# ELWireProximityController.net
KiCad netlist of a schematic drawn in EAGLE
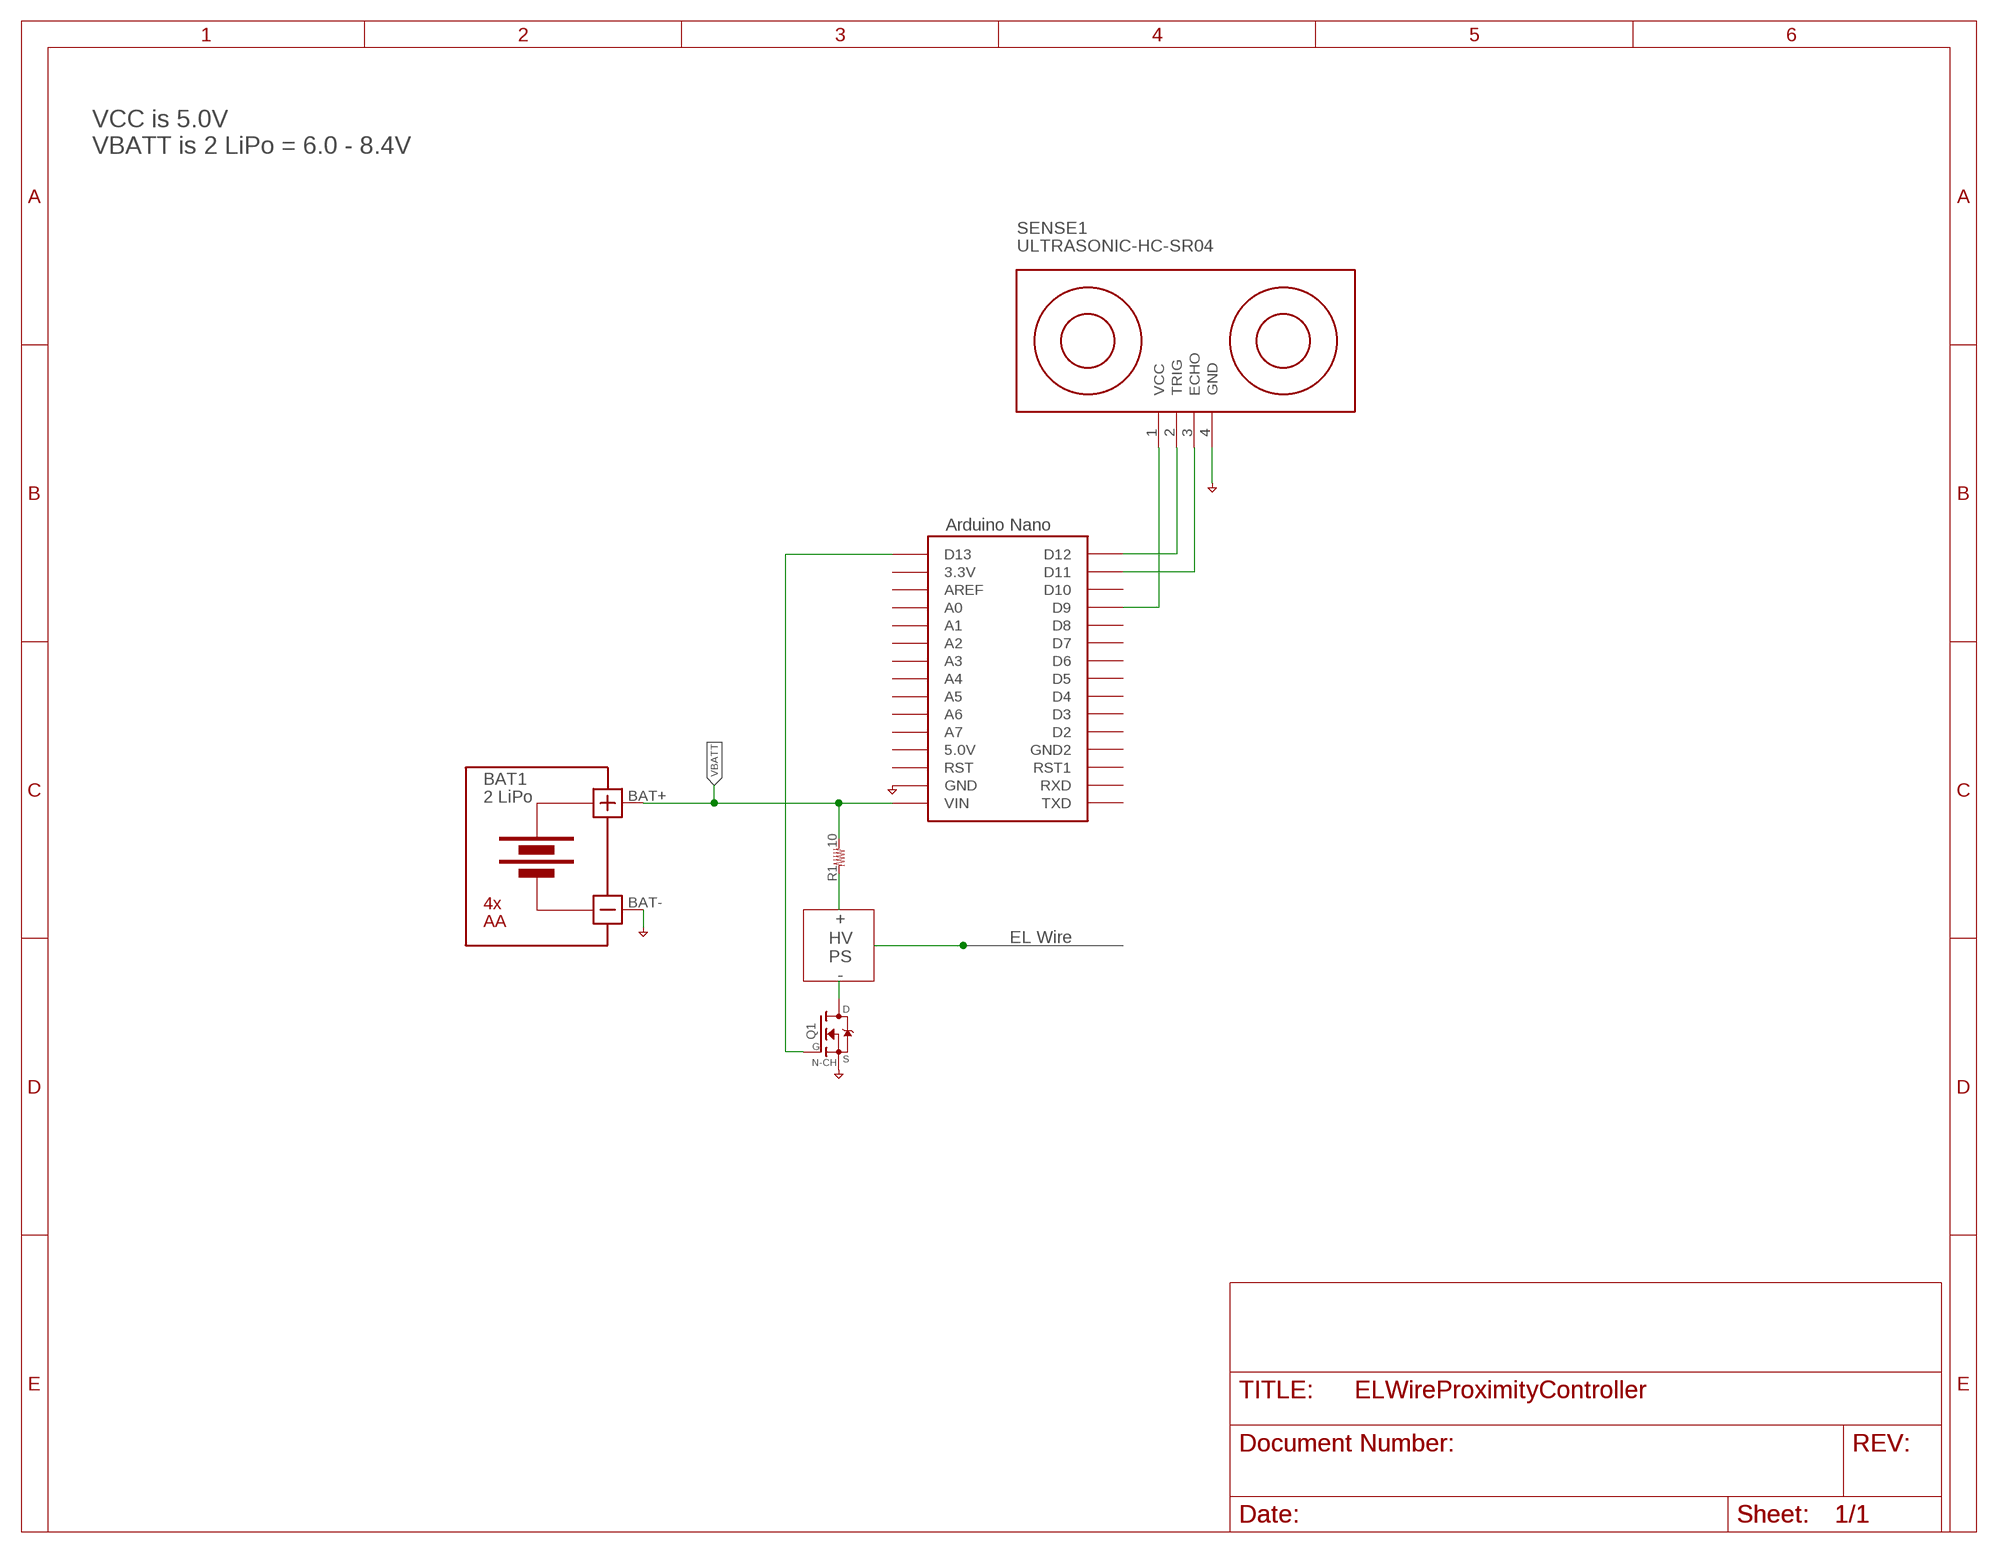
[diagram p0: schematic, sheet 1]

(export (version "E")
  (design (tool "Eeschema 10.0.6"))
  (components
    (comp (ref "BAT1")
      (value "2 LiPo")
      (footprint "eagle-import:BATTERY-HOLDER-2AA")
      (libsource (lib "eagle-import") (part "BATTERY-HOLDER-2AA"))
    )
    (comp (ref "Q1")
      (value "FET-NCH-SOT23")
      (footprint "eagle-import:SOT23-3")
      (libsource (lib "eagle-import") (part "FET-NCH-SOT23"))
    )
    (comp (ref "R1")
      (value "10")
      (footprint "eagle-import:R-THRU-H-0.4")
      (libsource (lib "eagle-import") (part "R-THRU-H-0.4"))
    )
    (comp (ref "SENSE1")
      (value "ULTRASONIC-HC-SR04")
      (footprint "eagle-import:ULTRASONIC-HC-SR04")
      (libsource (lib "eagle-import") (part "ULTRASONIC-HC-SR04"))
    )
    (comp (ref "U$1")
      (value "NANO")
      (footprint "eagle-import:NANO")
      (libsource (lib "eagle-import") (part "NANO"))
    )
  )
  (nets
    (net (code "1") (name "GND") (class "Default")
      (node (ref "BAT1") (pin "BAT-") (pinfunction "BAT-_BAT-") (pintype "power_in"))
      (node (ref "Q1") (pin "2") (pinfunction "S_2") (pintype "passive"))
      (node (ref "SENSE1") (pin "4") (pinfunction "GND_4") (pintype "power_in"))
      (node (ref "U$1") (pin "GND") (pinfunction "GND_GND") (pintype "bidirectional"))
    )
    (net (code "2") (name "Net-(Q1-G)") (class "Default")
      (node (ref "Q1") (pin "1") (pinfunction "G_1") (pintype "passive"))
      (node (ref "U$1") (pin "D13") (pinfunction "D13_D13") (pintype "bidirectional"))
    )
    (net (code "3") (name "Net-(SENSE1-ECHO)") (class "Default")
      (node (ref "SENSE1") (pin "3") (pinfunction "ECHO_3") (pintype "output"))
      (node (ref "U$1") (pin "D11") (pinfunction "D11_D11") (pintype "bidirectional"))
    )
    (net (code "4") (name "Net-(SENSE1-TRIG)") (class "Default")
      (node (ref "SENSE1") (pin "2") (pinfunction "TRIG_2") (pintype "input"))
      (node (ref "U$1") (pin "D12") (pinfunction "D12_D12") (pintype "bidirectional"))
    )
    (net (code "5") (name "Net-(SENSE1-VCC)") (class "Default")
      (node (ref "SENSE1") (pin "1") (pinfunction "VCC_1") (pintype "power_in"))
      (node (ref "U$1") (pin "D9") (pinfunction "D9_D9") (pintype "bidirectional"))
    )
    (net (code "6") (name "VBATT") (class "Default")
      (node (ref "BAT1") (pin "BAT+") (pinfunction "BAT+_BAT+") (pintype "power_in"))
      (node (ref "R1") (pin "2") (pinfunction "2_2") (pintype "passive"))
      (node (ref "U$1") (pin "RAW") (pinfunction "VIN_RAW") (pintype "bidirectional"))
    )
    (net (code "7") (name "unconnected-(Q1-D-Pad3)") (class "Default")
      (node (ref "Q1") (pin "3") (pinfunction "D_3") (pintype "passive"))
    )
    (net (code "8") (name "unconnected-(R1-Pad1)") (class "Default")
      (node (ref "R1") (pin "1") (pinfunction "1_1") (pintype "passive"))
    )
    (net (code "9") (name "unconnected-(U$1-5.0V-Pad5V)") (class "Default")
      (node (ref "U$1") (pin "5V") (pinfunction "5.0V_5V") (pintype "bidirectional"))
    )
    (net (code "10") (name "unconnected-(U$1-GND2-PadGND1)") (class "Default")
      (node (ref "U$1") (pin "GND1") (pinfunction "GND2_GND1") (pintype "bidirectional"))
    )
    (net (code "11") (name "unconnected-(U$1-Pad3.3V)") (class "Default")
      (node (ref "U$1") (pin "3.3V") (pinfunction "3.3V_3.3V") (pintype "bidirectional"))
    )
    (net (code "12") (name "unconnected-(U$1-PadA0)") (class "Default")
      (node (ref "U$1") (pin "A0") (pinfunction "A0_A0") (pintype "bidirectional"))
    )
    (net (code "13") (name "unconnected-(U$1-PadA1)") (class "Default")
      (node (ref "U$1") (pin "A1") (pinfunction "A1_A1") (pintype "bidirectional"))
    )
    (net (code "14") (name "unconnected-(U$1-PadA2)") (class "Default")
      (node (ref "U$1") (pin "A2") (pinfunction "A2_A2") (pintype "bidirectional"))
    )
    (net (code "15") (name "unconnected-(U$1-PadA3)") (class "Default")
      (node (ref "U$1") (pin "A3") (pinfunction "A3_A3") (pintype "bidirectional"))
    )
    (net (code "16") (name "unconnected-(U$1-PadA4)") (class "Default")
      (node (ref "U$1") (pin "A4") (pinfunction "A4_A4") (pintype "bidirectional"))
    )
    (net (code "17") (name "unconnected-(U$1-PadA5)") (class "Default")
      (node (ref "U$1") (pin "A5") (pinfunction "A5_A5") (pintype "bidirectional"))
    )
    (net (code "18") (name "unconnected-(U$1-PadA6)") (class "Default")
      (node (ref "U$1") (pin "A6") (pinfunction "A6_A6") (pintype "bidirectional"))
    )
    (net (code "19") (name "unconnected-(U$1-PadA7)") (class "Default")
      (node (ref "U$1") (pin "A7") (pinfunction "A7_A7") (pintype "bidirectional"))
    )
    (net (code "20") (name "unconnected-(U$1-PadAREF)") (class "Default")
      (node (ref "U$1") (pin "AREF") (pinfunction "AREF_AREF") (pintype "bidirectional"))
    )
    (net (code "21") (name "unconnected-(U$1-PadD2)") (class "Default")
      (node (ref "U$1") (pin "D2") (pinfunction "D2_D2") (pintype "bidirectional"))
    )
    (net (code "22") (name "unconnected-(U$1-PadD3)") (class "Default")
      (node (ref "U$1") (pin "D3") (pinfunction "D3_D3") (pintype "bidirectional"))
    )
    (net (code "23") (name "unconnected-(U$1-PadD4)") (class "Default")
      (node (ref "U$1") (pin "D4") (pinfunction "D4_D4") (pintype "bidirectional"))
    )
    (net (code "24") (name "unconnected-(U$1-PadD5)") (class "Default")
      (node (ref "U$1") (pin "D5") (pinfunction "D5_D5") (pintype "bidirectional"))
    )
    (net (code "25") (name "unconnected-(U$1-PadD6)") (class "Default")
      (node (ref "U$1") (pin "D6") (pinfunction "D6_D6") (pintype "bidirectional"))
    )
    (net (code "26") (name "unconnected-(U$1-PadD7)") (class "Default")
      (node (ref "U$1") (pin "D7") (pinfunction "D7_D7") (pintype "bidirectional"))
    )
    (net (code "27") (name "unconnected-(U$1-PadD8)") (class "Default")
      (node (ref "U$1") (pin "D8") (pinfunction "D8_D8") (pintype "bidirectional"))
    )
    (net (code "28") (name "unconnected-(U$1-PadD10)") (class "Default")
      (node (ref "U$1") (pin "D10") (pinfunction "D10_D10") (pintype "bidirectional"))
    )
    (net (code "29") (name "unconnected-(U$1-PadICSP1)") (class "Default")
      (node (ref "U$1") (pin "ICSP1") (pinfunction "ICSP1_ICSP1") (pintype "bidirectional"))
    )
    (net (code "30") (name "unconnected-(U$1-PadICSP2)") (class "Default")
      (node (ref "U$1") (pin "ICSP2") (pinfunction "ICSP2_ICSP2") (pintype "bidirectional"))
    )
    (net (code "31") (name "unconnected-(U$1-PadICSP3)") (class "Default")
      (node (ref "U$1") (pin "ICSP3") (pinfunction "ICSP3_ICSP3") (pintype "bidirectional"))
    )
    (net (code "32") (name "unconnected-(U$1-PadICSP4)") (class "Default")
      (node (ref "U$1") (pin "ICSP4") (pinfunction "ICSP4_ICSP4") (pintype "bidirectional"))
    )
    (net (code "33") (name "unconnected-(U$1-PadICSP5)") (class "Default")
      (node (ref "U$1") (pin "ICSP5") (pinfunction "ICSP5_ICSP5") (pintype "bidirectional"))
    )
    (net (code "34") (name "unconnected-(U$1-PadICSP6)") (class "Default")
      (node (ref "U$1") (pin "ICSP6") (pinfunction "ICSP6_ICSP6") (pintype "bidirectional"))
    )
    (net (code "35") (name "unconnected-(U$1-PadRST)") (class "Default")
      (node (ref "U$1") (pin "RST") (pinfunction "RST_RST") (pintype "bidirectional"))
    )
    (net (code "36") (name "unconnected-(U$1-PadRST1)") (class "Default")
      (node (ref "U$1") (pin "RST1") (pinfunction "RST1_RST1") (pintype "bidirectional"))
    )
    (net (code "37") (name "unconnected-(U$1-RXD-PadRX1)") (class "Default")
      (node (ref "U$1") (pin "RX1") (pinfunction "RXD_RX1") (pintype "bidirectional"))
    )
    (net (code "38") (name "unconnected-(U$1-TXD-PadTX0)") (class "Default")
      (node (ref "U$1") (pin "TX0") (pinfunction "TXD_TX0") (pintype "bidirectional"))
    )
  )
)
